# Sheet1.net
KiCad netlist of a schematic drawn in Altium Designer
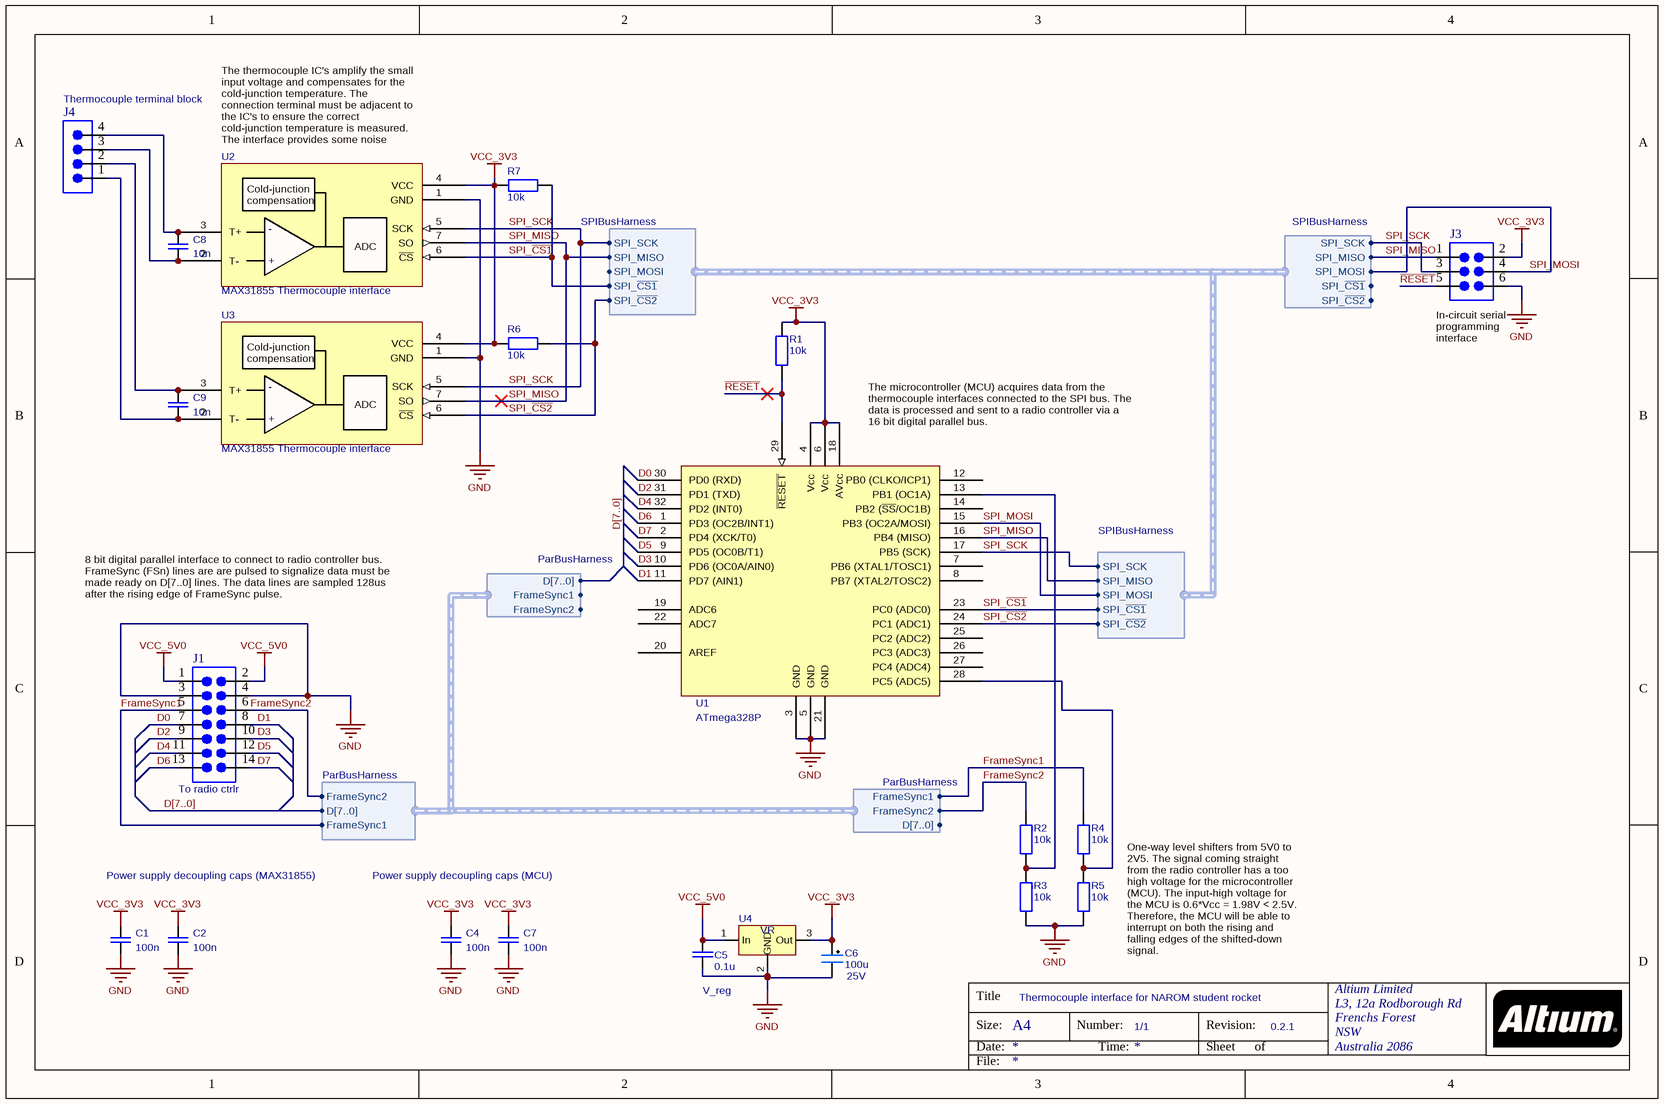
[diagram p0: Sheet1.SchDoc]

(export (version "E")
  (design (tool "Eeschema 10.0.6"))
  (components
    (comp (ref "C1")
      (value "100n")
      (footprint "cap_0603_standard")
      (description "Generic unipolarised capasitor")
      (libsource (lib "LabLib") (part "cap__genCapUnipol"))
    )
    (comp (ref "C2")
      (value "100n")
      (footprint "cap_0603_standard")
      (description "Generic unipolarised capasitor")
      (libsource (lib "LabLib") (part "cap__genCapUnipol"))
    )
    (comp (ref "C4")
      (value "100n")
      (footprint "cap_0603_standard")
      (description "Generic unipolarised capasitor")
      (libsource (lib "LabLib") (part "cap__genCapUnipol"))
    )
    (comp (ref "C5")
      (value "0.1u")
      (footprint "cap_0603_standard")
      (description "Generic unipolarised capasitor")
      (libsource (lib "LabLib") (part "cap__genCapUnipol"))
    )
    (comp (ref "C6")
      (value "100u")
      (footprint "cap_tantalum_eia_size_7343-31")
      (description "Generic polar capacitor")
      (fields (field (name "VOLTAGE RATING") "25V"))
      (libsource (lib "Schlib1") (part "cap_genCap_polar"))
    )
    (comp (ref "C7")
      (value "100n")
      (footprint "cap_0603_standard")
      (description "Generic unipolarised capasitor")
      (libsource (lib "LabLib") (part "cap__genCapUnipol"))
    )
    (comp (ref "C8")
      (value "10n")
      (footprint "cap_0603_standard")
      (description "Generic unipolarised capasitor")
      (libsource (lib "LabLib") (part "cap__genCapUnipol"))
    )
    (comp (ref "C9")
      (value "10n")
      (footprint "cap_0603_standard")
      (description "Generic unipolarised capasitor")
      (libsource (lib "LabLib") (part "cap__genCapUnipol"))
    )
    (comp (ref "J1")
      (value "To radio ctrlr")
      (footprint "con_datamate_2row_14pin")
      (description "Header 2x7pin")
      (libsource (lib "LabLib") (part "con_head_2x07pin"))
    )
    (comp (ref "J3")
      (value "Header 2x3pin")
      (footprint "HEADER_2X3")
      (libsource (lib "LabLib") (part "con_head_2x03pin"))
    )
    (comp (ref "J4")
      (value "Thermocouple terminal block")
      (footprint "con_harting_spring_cage_4way")
      (description "Header 1x4pin")
      (libsource (lib "LabLib") (part "con_head_1x04pin"))
    )
    (comp (ref "R1")
      (value "10k")
      (footprint "res_0603_standard")
      (description "Generic resistor")
      (libsource (lib "LabLib") (part "res__genResistor"))
    )
    (comp (ref "R2")
      (value "10k")
      (footprint "res_0603_standard")
      (description "Generic resistor")
      (libsource (lib "LabLib") (part "res__genResistor"))
    )
    (comp (ref "R3")
      (value "10k")
      (footprint "res_0603_standard")
      (description "Generic resistor")
      (libsource (lib "LabLib") (part "res__genResistor"))
    )
    (comp (ref "R4")
      (value "10k")
      (footprint "res_0603_standard")
      (description "Generic resistor")
      (libsource (lib "LabLib") (part "res__genResistor"))
    )
    (comp (ref "R5")
      (value "10k")
      (footprint "res_0603_standard")
      (description "Generic resistor")
      (libsource (lib "LabLib") (part "res__genResistor"))
    )
    (comp (ref "R6")
      (value "10k")
      (footprint "res_0603_standard")
      (description "Generic resistor")
      (libsource (lib "LabLib") (part "res__genResistor"))
    )
    (comp (ref "R7")
      (value "10k")
      (footprint "res_0603_standard")
      (description "Generic resistor")
      (libsource (lib "LabLib") (part "res__genResistor"))
    )
    (comp (ref "U1")
      (value "ATmega328P")
      (footprint "ic_atmel_atmega328p")
      (description "Atmel 8 bit microcontroller")
      (libsource (lib "Schlib1") (part "ic_atmel_atmega328p"))
    )
    (comp (ref "U2")
      (value "MAX31855 Thermocouple interface")
      (footprint "SO8_N")
      (description "Maxim MAX31855 thermocouple interface")
      (libsource (lib "Schlib1") (part "ic_maxim_max31855_thermocouple_interface_simplified"))
    )
    (comp (ref "U3")
      (value "MAX31855 Thermocouple interface")
      (footprint "SO8_N")
      (description "Maxim MAX31855 thermocouple interface")
      (libsource (lib "Schlib1") (part "ic_maxim_max31855_thermocouple_interface_simplified"))
    )
    (comp (ref "U4")
      (value "V_reg")
      (footprint "ic_lin_reg_lm3940_sot223")
      (description "Positive voltage regulator 78xx")
      (libsource (lib "LabLib") (part "ic_lin_vreg_LM78xx"))
    )
  )
  (nets
    (net (code "3") (name "/D0") (class "Default")
      (node (ref "J1") (pin "7") (pinfunction "7_7") (pintype "passive"))
      (node (ref "U1") (pin "30") (pinfunction "PD0_(RXD)_30") (pintype "passive"))
    )
    (net (code "4") (name "/D1") (class "Default")
      (node (ref "J1") (pin "8") (pinfunction "8_8") (pintype "passive"))
      (node (ref "U1") (pin "11") (pinfunction "PD7_(AIN1)_11") (pintype "passive"))
    )
    (net (code "5") (name "/D2") (class "Default")
      (node (ref "J1") (pin "9") (pinfunction "9_9") (pintype "passive"))
      (node (ref "U1") (pin "31") (pinfunction "PD1_(TXD)_31") (pintype "passive"))
    )
    (net (code "6") (name "/D3") (class "Default")
      (node (ref "J1") (pin "10") (pinfunction "10_10") (pintype "passive"))
      (node (ref "U1") (pin "10") (pinfunction "PD6_(OC0A/AIN0)_10") (pintype "passive"))
    )
    (net (code "7") (name "/D4") (class "Default")
      (node (ref "J1") (pin "11") (pinfunction "11_11") (pintype "passive"))
      (node (ref "U1") (pin "32") (pinfunction "PD2_(INT0)_32") (pintype "passive"))
    )
    (net (code "8") (name "/D5") (class "Default")
      (node (ref "J1") (pin "12") (pinfunction "12_12") (pintype "passive"))
      (node (ref "U1") (pin "9") (pinfunction "PD5_(OC0B/T1)_9") (pintype "passive"))
    )
    (net (code "9") (name "/D6") (class "Default")
      (node (ref "J1") (pin "13") (pinfunction "13_13") (pintype "passive"))
      (node (ref "U1") (pin "1") (pinfunction "PD3_(OC2B/INT1)_1") (pintype "passive"))
    )
    (net (code "10") (name "/D7") (class "Default")
      (node (ref "J1") (pin "14") (pinfunction "14_14") (pintype "passive"))
      (node (ref "U1") (pin "2") (pinfunction "PD4_(XCK/T0)_2") (pintype "passive"))
    )
    (net (code "12") (name "/FrameSync1") (class "Default")
      (node (ref "J1") (pin "5") (pinfunction "5_5") (pintype "passive"))
      (node (ref "R4") (pin "1") (pinfunction "1_1") (pintype "passive"))
    )
    (net (code "13") (name "/FrameSync2") (class "Default")
      (node (ref "J1") (pin "6") (pinfunction "6_6") (pintype "passive"))
      (node (ref "R2") (pin "1") (pinfunction "1_1") (pintype "passive"))
    )
    (net (code "14") (name "/SPI_MISO") (class "Default")
      (node (ref "J3") (pin "1") (pinfunction "1_1") (pintype "passive"))
      (node (ref "U1") (pin "16") (pinfunction "PB4_(MISO)_16") (pintype "passive"))
      (node (ref "U2") (pin "7") (pinfunction "SO_7") (pintype "output"))
      (node (ref "U3") (pin "7") (pinfunction "SO_7") (pintype "output"))
    )
    (net (code "15") (name "/SPI_MOSI") (class "Default")
      (node (ref "J3") (pin "4") (pinfunction "4_4") (pintype "passive"))
      (node (ref "U1") (pin "15") (pinfunction "PB3_(OC2A/MOSI)_15") (pintype "passive"))
    )
    (net (code "16") (name "/SPI_SCK") (class "Default")
      (node (ref "J3") (pin "3") (pinfunction "3_3") (pintype "passive"))
      (node (ref "U1") (pin "17") (pinfunction "PB5_(SCK)_17") (pintype "passive"))
      (node (ref "U2") (pin "5") (pinfunction "SCK_5") (pintype "input"))
      (node (ref "U3") (pin "5") (pinfunction "SCK_5") (pintype "input"))
    )
    (net (code "17") (name "/SPI_~{CS1}") (class "Default")
      (node (ref "R7") (pin "2") (pinfunction "2_2") (pintype "passive"))
      (node (ref "U1") (pin "23") (pinfunction "PC0_(ADC0)_23") (pintype "passive"))
      (node (ref "U2") (pin "6") (pinfunction "~{CS}_6") (pintype "input"))
    )
    (net (code "18") (name "/SPI_~{CS2}") (class "Default")
      (node (ref "R6") (pin "2") (pinfunction "2_2") (pintype "passive"))
      (node (ref "U1") (pin "24") (pinfunction "PC1_(ADC1)_24") (pintype "passive"))
      (node (ref "U3") (pin "6") (pinfunction "~{CS}_6") (pintype "input"))
    )
    (net (code "21") (name "/~{RESET}") (class "Default")
      (node (ref "J3") (pin "5") (pinfunction "5_5") (pintype "passive"))
      (node (ref "R1") (pin "2") (pinfunction "2_2") (pintype "passive"))
      (node (ref "U1") (pin "29") (pinfunction "~{RESET}_29") (pintype "input"))
    )
    (net (code "22") (name "GND") (class "Default")
      (node (ref "C1") (pin "1") (pinfunction "1_1") (pintype "passive"))
      (node (ref "C2") (pin "1") (pinfunction "1_1") (pintype "passive"))
      (node (ref "C4") (pin "1") (pinfunction "1_1") (pintype "passive"))
      (node (ref "C5") (pin "1") (pinfunction "1_1") (pintype "passive"))
      (node (ref "C6") (pin "2") (pintype "passive"))
      (node (ref "C7") (pin "1") (pinfunction "1_1") (pintype "passive"))
      (node (ref "J1") (pin "3") (pinfunction "3_3") (pintype "passive"))
      (node (ref "J1") (pin "4") (pinfunction "4_4") (pintype "passive"))
      (node (ref "J3") (pin "6") (pinfunction "6_6") (pintype "passive"))
      (node (ref "R3") (pin "2") (pinfunction "2_2") (pintype "passive"))
      (node (ref "R5") (pin "2") (pinfunction "2_2") (pintype "passive"))
      (node (ref "U1") (pin "21") (pinfunction "GND_21") (pintype "power_in"))
      (node (ref "U1") (pin "3") (pinfunction "GND_3") (pintype "power_in"))
      (node (ref "U1") (pin "5") (pinfunction "GND_5") (pintype "power_in"))
      (node (ref "U2") (pin "1") (pinfunction "GND_1") (pintype "power_in"))
      (node (ref "U3") (pin "1") (pinfunction "GND_1") (pintype "power_in"))
      (node (ref "U4") (pin "2") (pinfunction "GND_2") (pintype "passive"))
    )
    (net (code "23") (name "Net-(U1-PB1_(OC1A))") (class "Default")
      (node (ref "R2") (pin "2") (pinfunction "2_2") (pintype "passive"))
      (node (ref "R3") (pin "1") (pinfunction "1_1") (pintype "passive"))
      (node (ref "U1") (pin "13") (pinfunction "PB1_(OC1A)_13") (pintype "passive"))
    )
    (net (code "24") (name "Net-(U1-PC5_(ADC5))") (class "Default")
      (node (ref "R4") (pin "2") (pinfunction "2_2") (pintype "passive"))
      (node (ref "R5") (pin "1") (pinfunction "1_1") (pintype "passive"))
      (node (ref "U1") (pin "28") (pinfunction "PC5_(ADC5)_28") (pintype "passive"))
    )
    (net (code "25") (name "Net-(U2-T+)") (class "Default")
      (node (ref "C8") (pin "2") (pinfunction "2_2") (pintype "passive"))
      (node (ref "J4") (pin "4") (pinfunction "4_4") (pintype "passive"))
      (node (ref "U2") (pin "3") (pinfunction "T+_3") (pintype "passive"))
    )
    (net (code "26") (name "Net-(U2-T-)") (class "Default")
      (node (ref "C8") (pin "1") (pinfunction "1_1") (pintype "passive"))
      (node (ref "J4") (pin "3") (pinfunction "3_3") (pintype "passive"))
      (node (ref "U2") (pin "2") (pinfunction "T-_2") (pintype "passive"))
    )
    (net (code "27") (name "Net-(U3-T+)") (class "Default")
      (node (ref "C9") (pin "2") (pinfunction "2_2") (pintype "passive"))
      (node (ref "J4") (pin "2") (pinfunction "2_2") (pintype "passive"))
      (node (ref "U3") (pin "3") (pinfunction "T+_3") (pintype "passive"))
    )
    (net (code "28") (name "Net-(U3-T-)") (class "Default")
      (node (ref "C9") (pin "1") (pinfunction "1_1") (pintype "passive"))
      (node (ref "J4") (pin "1") (pinfunction "1_1") (pintype "passive"))
      (node (ref "U3") (pin "2") (pinfunction "T-_2") (pintype "passive"))
    )
    (net (code "29") (name "VCC_3V3") (class "Default")
      (node (ref "C1") (pin "2") (pinfunction "2_2") (pintype "passive"))
      (node (ref "C2") (pin "2") (pinfunction "2_2") (pintype "passive"))
      (node (ref "C4") (pin "2") (pinfunction "2_2") (pintype "passive"))
      (node (ref "C6") (pin "1") (pintype "passive"))
      (node (ref "C7") (pin "2") (pinfunction "2_2") (pintype "passive"))
      (node (ref "J3") (pin "2") (pinfunction "2_2") (pintype "passive"))
      (node (ref "R1") (pin "1") (pinfunction "1_1") (pintype "passive"))
      (node (ref "R6") (pin "1") (pinfunction "1_1") (pintype "passive"))
      (node (ref "R7") (pin "1") (pinfunction "1_1") (pintype "passive"))
      (node (ref "U1") (pin "18") (pinfunction "AVcc_18") (pintype "power_in"))
      (node (ref "U1") (pin "4") (pinfunction "Vcc_4") (pintype "power_in"))
      (node (ref "U1") (pin "6") (pinfunction "Vcc_6") (pintype "power_in"))
      (node (ref "U2") (pin "4") (pinfunction "VCC_4") (pintype "power_in"))
      (node (ref "U3") (pin "4") (pinfunction "VCC_4") (pintype "power_in"))
      (node (ref "U4") (pin "3") (pinfunction "Out_3") (pintype "passive"))
    )
    (net (code "30") (name "VCC_5V0") (class "Default")
      (node (ref "C5") (pin "2") (pinfunction "2_2") (pintype "passive"))
      (node (ref "J1") (pin "1") (pinfunction "1_1") (pintype "passive"))
      (node (ref "J1") (pin "2") (pinfunction "2_2") (pintype "passive"))
      (node (ref "U4") (pin "1") (pinfunction "In_1") (pintype "passive"))
    )
    (net (code "31") (name "unconnected-(U1-ADC6-Pad19)") (class "Default")
      (node (ref "U1") (pin "19") (pinfunction "ADC6_19") (pintype "passive"))
    )
    (net (code "32") (name "unconnected-(U1-ADC7-Pad22)") (class "Default")
      (node (ref "U1") (pin "22") (pinfunction "ADC7_22") (pintype "passive"))
    )
    (net (code "33") (name "unconnected-(U1-AREF-Pad20)") (class "Default")
      (node (ref "U1") (pin "20") (pinfunction "AREF_20") (pintype "passive"))
    )
    (net (code "34") (name "unconnected-(U1-PB0_(CLKO{slash}ICP1)-Pad12)") (class "Default")
      (node (ref "U1") (pin "12") (pinfunction "PB0_(CLKO/ICP1)_12") (pintype "passive"))
    )
    (net (code "35") (name "unconnected-(U1-PB2_(~{SS}{slash}OC1B)-Pad14)") (class "Default")
      (node (ref "U1") (pin "14") (pinfunction "PB2_(~{SS}/OC1B)_14") (pintype "passive"))
    )
    (net (code "36") (name "unconnected-(U1-PB6_(XTAL1{slash}TOSC1)-Pad7)") (class "Default")
      (node (ref "U1") (pin "7") (pinfunction "PB6_(XTAL1/TOSC1)_7") (pintype "passive"))
    )
    (net (code "37") (name "unconnected-(U1-PB7_(XTAL2{slash}TOSC2)-Pad8)") (class "Default")
      (node (ref "U1") (pin "8") (pinfunction "PB7_(XTAL2/TOSC2)_8") (pintype "passive"))
    )
    (net (code "38") (name "unconnected-(U1-PC2_(ADC2)-Pad25)") (class "Default")
      (node (ref "U1") (pin "25") (pinfunction "PC2_(ADC2)_25") (pintype "passive"))
    )
    (net (code "39") (name "unconnected-(U1-PC3_(ADC3)-Pad26)") (class "Default")
      (node (ref "U1") (pin "26") (pinfunction "PC3_(ADC3)_26") (pintype "passive"))
    )
    (net (code "40") (name "unconnected-(U1-PC4_(ADC4)-Pad27)") (class "Default")
      (node (ref "U1") (pin "27") (pinfunction "PC4_(ADC4)_27") (pintype "passive"))
    )
  )
)
